# barrieren-a-1.net
KiCad netlist of a schematic drawn in EAGLE
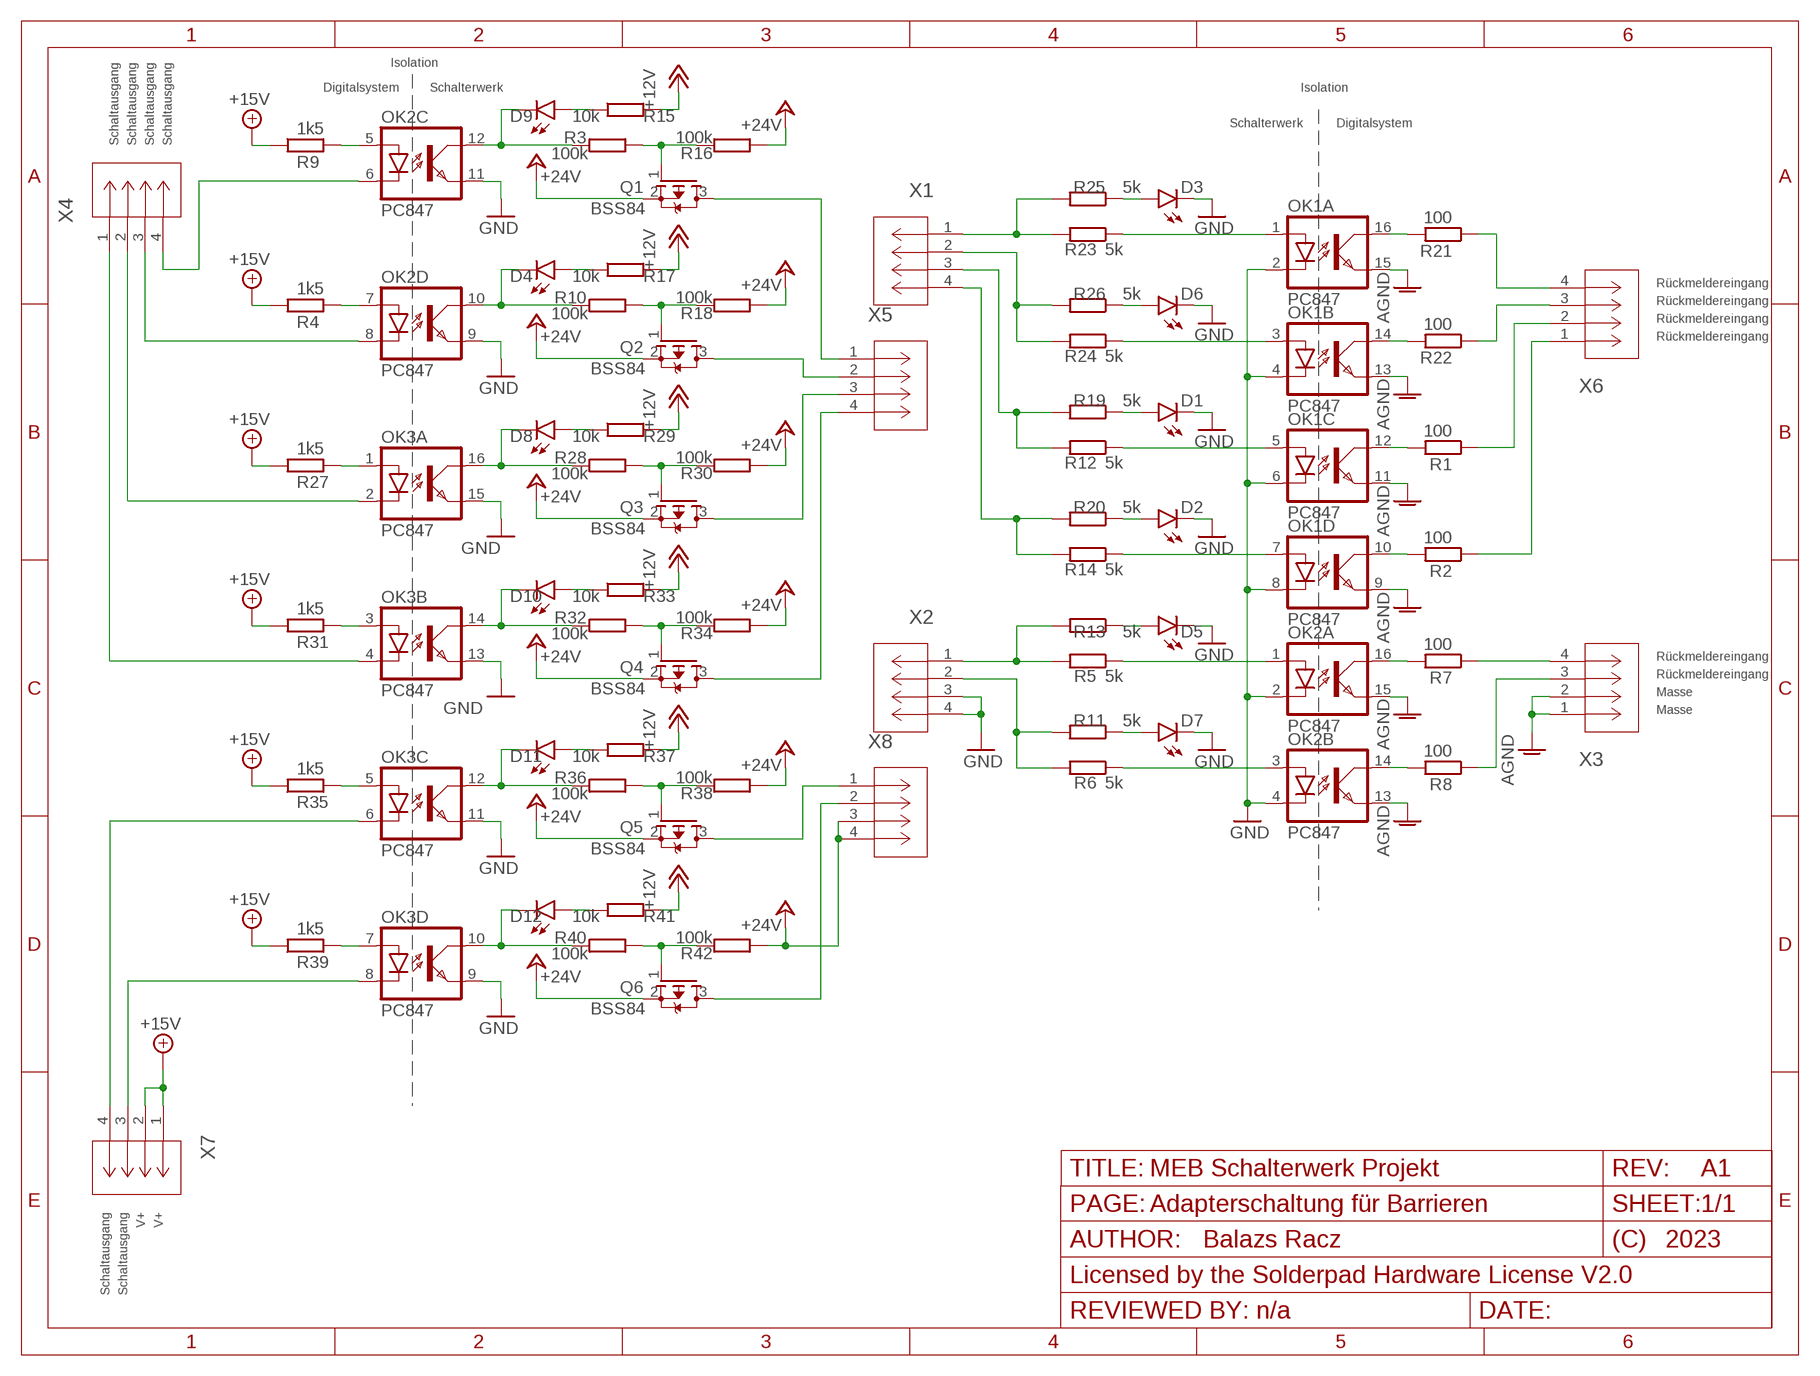
[diagram p0: schematic, sheet 1]

(export (version "E")
  (design (tool "Eeschema 10.0.6"))
  (components
    (comp (ref "D1")
      (value "LEDCHIPLED_0603")
      (footprint "eagle-import:CHIPLED_0603")
      (libsource (lib "eagle-import") (part "LEDCHIPLED_0603"))
    )
    (comp (ref "D2")
      (value "LEDCHIPLED_0603")
      (footprint "eagle-import:CHIPLED_0603")
      (libsource (lib "eagle-import") (part "LEDCHIPLED_0603"))
    )
    (comp (ref "D3")
      (value "LEDCHIPLED_0603")
      (footprint "eagle-import:CHIPLED_0603")
      (libsource (lib "eagle-import") (part "LEDCHIPLED_0603"))
    )
    (comp (ref "D4")
      (value "LEDCHIPLED_0603")
      (footprint "eagle-import:CHIPLED_0603")
      (libsource (lib "eagle-import") (part "LEDCHIPLED_0603"))
    )
    (comp (ref "D5")
      (value "LEDCHIPLED_0603")
      (footprint "eagle-import:CHIPLED_0603")
      (libsource (lib "eagle-import") (part "LEDCHIPLED_0603"))
    )
    (comp (ref "D6")
      (value "LEDCHIPLED_0603")
      (footprint "eagle-import:CHIPLED_0603")
      (libsource (lib "eagle-import") (part "LEDCHIPLED_0603"))
    )
    (comp (ref "D7")
      (value "LEDCHIPLED_0603")
      (footprint "eagle-import:CHIPLED_0603")
      (libsource (lib "eagle-import") (part "LEDCHIPLED_0603"))
    )
    (comp (ref "D8")
      (value "LEDCHIPLED_0603")
      (footprint "eagle-import:CHIPLED_0603")
      (libsource (lib "eagle-import") (part "LEDCHIPLED_0603"))
    )
    (comp (ref "D9")
      (value "LEDCHIPLED_0603")
      (footprint "eagle-import:CHIPLED_0603")
      (libsource (lib "eagle-import") (part "LEDCHIPLED_0603"))
    )
    (comp (ref "D10")
      (value "LEDCHIPLED_0603")
      (footprint "eagle-import:CHIPLED_0603")
      (libsource (lib "eagle-import") (part "LEDCHIPLED_0603"))
    )
    (comp (ref "D11")
      (value "LEDCHIPLED_0603")
      (footprint "eagle-import:CHIPLED_0603")
      (libsource (lib "eagle-import") (part "LEDCHIPLED_0603"))
    )
    (comp (ref "D12")
      (value "LEDCHIPLED_0603")
      (footprint "eagle-import:CHIPLED_0603")
      (libsource (lib "eagle-import") (part "LEDCHIPLED_0603"))
    )
    (comp (ref "OK1")
      (value "PC847")
      (footprint "eagle-import:DIL16")
      (libsource (lib "eagle-import") (part "PC847"))
    )
    (comp (ref "OK2")
      (value "PC847")
      (footprint "eagle-import:DIL16")
      (libsource (lib "eagle-import") (part "PC847"))
    )
    (comp (ref "OK3")
      (value "PC847")
      (footprint "eagle-import:DIL16")
      (libsource (lib "eagle-import") (part "PC847"))
    )
    (comp (ref "Q1")
      (value "BSS84")
      (footprint "eagle-import:SOT23-PCH")
      (libsource (lib "eagle-import") (part "BSS84"))
    )
    (comp (ref "Q2")
      (value "BSS84")
      (footprint "eagle-import:SOT23-PCH")
      (libsource (lib "eagle-import") (part "BSS84"))
    )
    (comp (ref "Q3")
      (value "BSS84")
      (footprint "eagle-import:SOT23-PCH")
      (libsource (lib "eagle-import") (part "BSS84"))
    )
    (comp (ref "Q4")
      (value "BSS84")
      (footprint "eagle-import:SOT23-PCH")
      (libsource (lib "eagle-import") (part "BSS84"))
    )
    (comp (ref "Q5")
      (value "BSS84")
      (footprint "eagle-import:SOT23-PCH")
      (libsource (lib "eagle-import") (part "BSS84"))
    )
    (comp (ref "Q6")
      (value "BSS84")
      (footprint "eagle-import:SOT23-PCH")
      (libsource (lib "eagle-import") (part "BSS84"))
    )
    (comp (ref "R1")
      (value "100")
      (footprint "eagle-import:R0805")
      (libsource (lib "eagle-import") (part "R-EU_R0805"))
    )
    (comp (ref "R2")
      (value "100")
      (footprint "eagle-import:R0805")
      (libsource (lib "eagle-import") (part "R-EU_R0805"))
    )
    (comp (ref "R3")
      (value "100k")
      (footprint "eagle-import:R0805")
      (libsource (lib "eagle-import") (part "R-EU_R0805"))
    )
    (comp (ref "R4")
      (value "1k5")
      (footprint "eagle-import:R0805")
      (libsource (lib "eagle-import") (part "R-EU_R0805"))
    )
    (comp (ref "R5")
      (value "5k")
      (footprint "eagle-import:R0805")
      (libsource (lib "eagle-import") (part "R-EU_R0805"))
    )
    (comp (ref "R6")
      (value "5k")
      (footprint "eagle-import:R0805")
      (libsource (lib "eagle-import") (part "R-EU_R0805"))
    )
    (comp (ref "R7")
      (value "100")
      (footprint "eagle-import:R0805")
      (libsource (lib "eagle-import") (part "R-EU_R0805"))
    )
    (comp (ref "R8")
      (value "100")
      (footprint "eagle-import:R0805")
      (libsource (lib "eagle-import") (part "R-EU_R0805"))
    )
    (comp (ref "R9")
      (value "1k5")
      (footprint "eagle-import:R0805")
      (libsource (lib "eagle-import") (part "R-EU_R0805"))
    )
    (comp (ref "R10")
      (value "100k")
      (footprint "eagle-import:R0805")
      (libsource (lib "eagle-import") (part "R-EU_R0805"))
    )
    (comp (ref "R11")
      (value "5k")
      (footprint "eagle-import:R0805")
      (libsource (lib "eagle-import") (part "R-EU_R0805"))
    )
    (comp (ref "R12")
      (value "5k")
      (footprint "eagle-import:R0805")
      (libsource (lib "eagle-import") (part "R-EU_R0805"))
    )
    (comp (ref "R13")
      (value "5k")
      (footprint "eagle-import:R0805")
      (libsource (lib "eagle-import") (part "R-EU_R0805"))
    )
    (comp (ref "R14")
      (value "5k")
      (footprint "eagle-import:R0805")
      (libsource (lib "eagle-import") (part "R-EU_R0805"))
    )
    (comp (ref "R15")
      (value "10k")
      (footprint "eagle-import:R0805")
      (libsource (lib "eagle-import") (part "R-EU_R0805"))
    )
    (comp (ref "R16")
      (value "100k")
      (footprint "eagle-import:R0805")
      (libsource (lib "eagle-import") (part "R-EU_R0805"))
    )
    (comp (ref "R17")
      (value "10k")
      (footprint "eagle-import:R0805")
      (libsource (lib "eagle-import") (part "R-EU_R0805"))
    )
    (comp (ref "R18")
      (value "100k")
      (footprint "eagle-import:R0805")
      (libsource (lib "eagle-import") (part "R-EU_R0805"))
    )
    (comp (ref "R19")
      (value "5k")
      (footprint "eagle-import:R0805")
      (libsource (lib "eagle-import") (part "R-EU_R0805"))
    )
    (comp (ref "R20")
      (value "5k")
      (footprint "eagle-import:R0805")
      (libsource (lib "eagle-import") (part "R-EU_R0805"))
    )
    (comp (ref "R21")
      (value "100")
      (footprint "eagle-import:R0805")
      (libsource (lib "eagle-import") (part "R-EU_R0805"))
    )
    (comp (ref "R22")
      (value "100")
      (footprint "eagle-import:R0805")
      (libsource (lib "eagle-import") (part "R-EU_R0805"))
    )
    (comp (ref "R23")
      (value "5k")
      (footprint "eagle-import:R0805")
      (libsource (lib "eagle-import") (part "R-EU_R0805"))
    )
    (comp (ref "R24")
      (value "5k")
      (footprint "eagle-import:R0805")
      (libsource (lib "eagle-import") (part "R-EU_R0805"))
    )
    (comp (ref "R25")
      (value "5k")
      (footprint "eagle-import:R0805")
      (libsource (lib "eagle-import") (part "R-EU_R0805"))
    )
    (comp (ref "R26")
      (value "5k")
      (footprint "eagle-import:R0805")
      (libsource (lib "eagle-import") (part "R-EU_R0805"))
    )
    (comp (ref "R27")
      (value "1k5")
      (footprint "eagle-import:R0805")
      (libsource (lib "eagle-import") (part "R-EU_R0805"))
    )
    (comp (ref "R28")
      (value "100k")
      (footprint "eagle-import:R0805")
      (libsource (lib "eagle-import") (part "R-EU_R0805"))
    )
    (comp (ref "R29")
      (value "10k")
      (footprint "eagle-import:R0805")
      (libsource (lib "eagle-import") (part "R-EU_R0805"))
    )
    (comp (ref "R30")
      (value "100k")
      (footprint "eagle-import:R0805")
      (libsource (lib "eagle-import") (part "R-EU_R0805"))
    )
    (comp (ref "R31")
      (value "1k5")
      (footprint "eagle-import:R0805")
      (libsource (lib "eagle-import") (part "R-EU_R0805"))
    )
    (comp (ref "R32")
      (value "100k")
      (footprint "eagle-import:R0805")
      (libsource (lib "eagle-import") (part "R-EU_R0805"))
    )
    (comp (ref "R33")
      (value "10k")
      (footprint "eagle-import:R0805")
      (libsource (lib "eagle-import") (part "R-EU_R0805"))
    )
    (comp (ref "R34")
      (value "100k")
      (footprint "eagle-import:R0805")
      (libsource (lib "eagle-import") (part "R-EU_R0805"))
    )
    (comp (ref "R35")
      (value "1k5")
      (footprint "eagle-import:R0805")
      (libsource (lib "eagle-import") (part "R-EU_R0805"))
    )
    (comp (ref "R36")
      (value "100k")
      (footprint "eagle-import:R0805")
      (libsource (lib "eagle-import") (part "R-EU_R0805"))
    )
    (comp (ref "R37")
      (value "10k")
      (footprint "eagle-import:R0805")
      (libsource (lib "eagle-import") (part "R-EU_R0805"))
    )
    (comp (ref "R38")
      (value "100k")
      (footprint "eagle-import:R0805")
      (libsource (lib "eagle-import") (part "R-EU_R0805"))
    )
    (comp (ref "R39")
      (value "1k5")
      (footprint "eagle-import:R0805")
      (libsource (lib "eagle-import") (part "R-EU_R0805"))
    )
    (comp (ref "R40")
      (value "100k")
      (footprint "eagle-import:R0805")
      (libsource (lib "eagle-import") (part "R-EU_R0805"))
    )
    (comp (ref "R41")
      (value "10k")
      (footprint "eagle-import:R0805")
      (libsource (lib "eagle-import") (part "R-EU_R0805"))
    )
    (comp (ref "R42")
      (value "100k")
      (footprint "eagle-import:R0805")
      (libsource (lib "eagle-import") (part "R-EU_R0805"))
    )
    (comp (ref "X1")
      (value "PHNX_4P_350CONN_1984989_PXC")
      (footprint "eagle-import:PHNX_4P_350")
      (fields
        (field (name "MANUFACTURER_PART_NUMBER") "1984989")
        (field (name "COPYRIGHT") "Copyright (C) 2023 Ultra Librarian. All rights reserved.")
      )
      (libsource (lib "eagle-import") (part "PHNX_4P_350CONN_1984989_PXC"))
    )
    (comp (ref "X2")
      (value "PHNX_4P_350CONN_1984989_PXC")
      (footprint "eagle-import:PHNX_4P_350")
      (fields
        (field (name "MANUFACTURER_PART_NUMBER") "1984989")
        (field (name "COPYRIGHT") "Copyright (C) 2023 Ultra Librarian. All rights reserved.")
      )
      (libsource (lib "eagle-import") (part "PHNX_4P_350CONN_1984989_PXC"))
    )
    (comp (ref "X3")
      (value "PHNX_4P_350CONN_1984989_PXC")
      (footprint "eagle-import:PHNX_4P_350")
      (fields
        (field (name "MANUFACTURER_PART_NUMBER") "1984989")
        (field (name "COPYRIGHT") "Copyright (C) 2023 Ultra Librarian. All rights reserved.")
      )
      (libsource (lib "eagle-import") (part "PHNX_4P_350CONN_1984989_PXC"))
    )
    (comp (ref "X4")
      (value "PHNX_4P_350CONN_1984989_PXC")
      (footprint "eagle-import:PHNX_4P_350")
      (fields
        (field (name "MANUFACTURER_PART_NUMBER") "1984989")
        (field (name "COPYRIGHT") "Copyright (C) 2023 Ultra Librarian. All rights reserved.")
      )
      (libsource (lib "eagle-import") (part "PHNX_4P_350CONN_1984989_PXC"))
    )
    (comp (ref "X5")
      (value "PHNX_4P_350CONN_1984989_PXC")
      (footprint "eagle-import:PHNX_4P_350")
      (fields
        (field (name "MANUFACTURER_PART_NUMBER") "1984989")
        (field (name "COPYRIGHT") "Copyright (C) 2023 Ultra Librarian. All rights reserved.")
      )
      (libsource (lib "eagle-import") (part "PHNX_4P_350CONN_1984989_PXC"))
    )
    (comp (ref "X6")
      (value "PHNX_4P_350CONN_1984989_PXC")
      (footprint "eagle-import:PHNX_4P_350")
      (fields
        (field (name "MANUFACTURER_PART_NUMBER") "1984989")
        (field (name "COPYRIGHT") "Copyright (C) 2023 Ultra Librarian. All rights reserved.")
      )
      (libsource (lib "eagle-import") (part "PHNX_4P_350CONN_1984989_PXC"))
    )
    (comp (ref "X7")
      (value "PHNX_4P_350CONN_1984989_PXC")
      (footprint "eagle-import:PHNX_4P_350")
      (fields
        (field (name "MANUFACTURER_PART_NUMBER") "1984989")
        (field (name "COPYRIGHT") "Copyright (C) 2023 Ultra Librarian. All rights reserved.")
      )
      (libsource (lib "eagle-import") (part "PHNX_4P_350CONN_1984989_PXC"))
    )
    (comp (ref "X8")
      (value "PHNX_4P_350CONN_1984989_PXC")
      (footprint "eagle-import:PHNX_4P_350")
      (fields
        (field (name "MANUFACTURER_PART_NUMBER") "1984989")
        (field (name "COPYRIGHT") "Copyright (C) 2023 Ultra Librarian. All rights reserved.")
      )
      (libsource (lib "eagle-import") (part "PHNX_4P_350CONN_1984989_PXC"))
    )
  )
  (nets
    (net (code "1") (name "+12V") (class "Default")
      (node (ref "R15") (pin "2") (pinfunction "2_2") (pintype "passive"))
      (node (ref "R17") (pin "2") (pinfunction "2_2") (pintype "passive"))
      (node (ref "R29") (pin "2") (pinfunction "2_2") (pintype "passive"))
      (node (ref "R33") (pin "2") (pinfunction "2_2") (pintype "passive"))
      (node (ref "R37") (pin "2") (pinfunction "2_2") (pintype "passive"))
      (node (ref "R41") (pin "2") (pinfunction "2_2") (pintype "passive"))
    )
    (net (code "2") (name "+15V") (class "Default")
      (node (ref "R27") (pin "1") (pinfunction "1_1") (pintype "passive"))
      (node (ref "R31") (pin "1") (pinfunction "1_1") (pintype "passive"))
      (node (ref "R35") (pin "1") (pinfunction "1_1") (pintype "passive"))
      (node (ref "R39") (pin "1") (pinfunction "1_1") (pintype "passive"))
      (node (ref "R4") (pin "1") (pinfunction "1_1") (pintype "passive"))
      (node (ref "R9") (pin "1") (pinfunction "1_1") (pintype "passive"))
      (node (ref "X7") (pin "1") (pinfunction "1_1") (pintype "passive"))
      (node (ref "X7") (pin "2") (pinfunction "2_2") (pintype "passive"))
    )
    (net (code "3") (name "+24V") (class "Default")
      (node (ref "Q1") (pin "2") (pinfunction "S_2") (pintype "passive"))
      (node (ref "Q2") (pin "2") (pinfunction "S_2") (pintype "passive"))
      (node (ref "Q3") (pin "2") (pinfunction "S_2") (pintype "passive"))
      (node (ref "Q4") (pin "2") (pinfunction "S_2") (pintype "passive"))
      (node (ref "Q5") (pin "2") (pinfunction "S_2") (pintype "passive"))
      (node (ref "Q6") (pin "2") (pinfunction "S_2") (pintype "passive"))
      (node (ref "R16") (pin "2") (pinfunction "2_2") (pintype "passive"))
      (node (ref "R18") (pin "2") (pinfunction "2_2") (pintype "passive"))
      (node (ref "R30") (pin "2") (pinfunction "2_2") (pintype "passive"))
      (node (ref "R34") (pin "2") (pinfunction "2_2") (pintype "passive"))
      (node (ref "R38") (pin "2") (pinfunction "2_2") (pintype "passive"))
      (node (ref "R42") (pin "2") (pinfunction "2_2") (pintype "passive"))
      (node (ref "X8") (pin "3") (pinfunction "3_3") (pintype "passive"))
      (node (ref "X8") (pin "4") (pinfunction "4_4") (pintype "passive"))
    )
    (net (code "4") (name "AGND") (class "Default")
      (node (ref "OK1") (pin "11") (pinfunction "EMIT_11") (pintype "passive"))
      (node (ref "OK1") (pin "13") (pinfunction "EMIT_13") (pintype "passive"))
      (node (ref "OK1") (pin "15") (pinfunction "EMIT_15") (pintype "passive"))
      (node (ref "OK1") (pin "9") (pinfunction "EMIT_9") (pintype "passive"))
      (node (ref "OK2") (pin "13") (pinfunction "EMIT_13") (pintype "passive"))
      (node (ref "OK2") (pin "15") (pinfunction "EMIT_15") (pintype "passive"))
      (node (ref "X3") (pin "1") (pinfunction "1_1") (pintype "passive"))
      (node (ref "X3") (pin "2") (pinfunction "2_2") (pintype "passive"))
    )
    (net (code "5") (name "GND") (class "Default")
      (node (ref "D1") (pin "C") (pinfunction "C_C") (pintype "passive"))
      (node (ref "D2") (pin "C") (pinfunction "C_C") (pintype "passive"))
      (node (ref "D3") (pin "C") (pinfunction "C_C") (pintype "passive"))
      (node (ref "D5") (pin "C") (pinfunction "C_C") (pintype "passive"))
      (node (ref "D6") (pin "C") (pinfunction "C_C") (pintype "passive"))
      (node (ref "D7") (pin "C") (pinfunction "C_C") (pintype "passive"))
      (node (ref "OK1") (pin "2") (pinfunction "C_2") (pintype "passive"))
      (node (ref "OK1") (pin "4") (pinfunction "C_4") (pintype "passive"))
      (node (ref "OK1") (pin "6") (pinfunction "C_6") (pintype "passive"))
      (node (ref "OK1") (pin "8") (pinfunction "C_8") (pintype "passive"))
      (node (ref "OK2") (pin "11") (pinfunction "EMIT_11") (pintype "passive"))
      (node (ref "OK2") (pin "2") (pinfunction "C_2") (pintype "passive"))
      (node (ref "OK2") (pin "4") (pinfunction "C_4") (pintype "passive"))
      (node (ref "OK2") (pin "9") (pinfunction "EMIT_9") (pintype "passive"))
      (node (ref "OK3") (pin "11") (pinfunction "EMIT_11") (pintype "passive"))
      (node (ref "OK3") (pin "13") (pinfunction "EMIT_13") (pintype "passive"))
      (node (ref "OK3") (pin "15") (pinfunction "EMIT_15") (pintype "passive"))
      (node (ref "OK3") (pin "9") (pinfunction "EMIT_9") (pintype "passive"))
      (node (ref "X2") (pin "3") (pinfunction "3_3") (pintype "passive"))
      (node (ref "X2") (pin "4") (pinfunction "4_4") (pintype "passive"))
    )
    (net (code "6") (name "Net-(D1-PadA)") (class "Default")
      (node (ref "D1") (pin "A") (pinfunction "A_A") (pintype "passive"))
      (node (ref "R19") (pin "1") (pinfunction "1_1") (pintype "passive"))
    )
    (net (code "7") (name "Net-(D2-PadA)") (class "Default")
      (node (ref "D2") (pin "A") (pinfunction "A_A") (pintype "passive"))
      (node (ref "R20") (pin "1") (pinfunction "1_1") (pintype "passive"))
    )
    (net (code "8") (name "Net-(D3-PadA)") (class "Default")
      (node (ref "D3") (pin "A") (pinfunction "A_A") (pintype "passive"))
      (node (ref "R25") (pin "1") (pinfunction "1_1") (pintype "passive"))
    )
    (net (code "9") (name "Net-(D4-PadA)") (class "Default")
      (node (ref "D4") (pin "A") (pinfunction "A_A") (pintype "passive"))
      (node (ref "R17") (pin "1") (pinfunction "1_1") (pintype "passive"))
    )
    (net (code "10") (name "Net-(D5-PadA)") (class "Default")
      (node (ref "D5") (pin "A") (pinfunction "A_A") (pintype "passive"))
      (node (ref "R13") (pin "1") (pinfunction "1_1") (pintype "passive"))
    )
    (net (code "11") (name "Net-(D6-PadA)") (class "Default")
      (node (ref "D6") (pin "A") (pinfunction "A_A") (pintype "passive"))
      (node (ref "R26") (pin "1") (pinfunction "1_1") (pintype "passive"))
    )
    (net (code "12") (name "Net-(D7-PadA)") (class "Default")
      (node (ref "D7") (pin "A") (pinfunction "A_A") (pintype "passive"))
      (node (ref "R11") (pin "1") (pinfunction "1_1") (pintype "passive"))
    )
    (net (code "13") (name "Net-(D8-PadA)") (class "Default")
      (node (ref "D8") (pin "A") (pinfunction "A_A") (pintype "passive"))
      (node (ref "R29") (pin "1") (pinfunction "1_1") (pintype "passive"))
    )
    (net (code "14") (name "Net-(D9-PadA)") (class "Default")
      (node (ref "D9") (pin "A") (pinfunction "A_A") (pintype "passive"))
      (node (ref "R15") (pin "1") (pinfunction "1_1") (pintype "passive"))
    )
    (net (code "15") (name "Net-(D10-PadA)") (class "Default")
      (node (ref "D10") (pin "A") (pinfunction "A_A") (pintype "passive"))
      (node (ref "R33") (pin "1") (pinfunction "1_1") (pintype "passive"))
    )
    (net (code "16") (name "Net-(D11-PadA)") (class "Default")
      (node (ref "D11") (pin "A") (pinfunction "A_A") (pintype "passive"))
      (node (ref "R37") (pin "1") (pinfunction "1_1") (pintype "passive"))
    )
    (net (code "17") (name "Net-(D12-PadA)") (class "Default")
      (node (ref "D12") (pin "A") (pinfunction "A_A") (pintype "passive"))
      (node (ref "R41") (pin "1") (pinfunction "1_1") (pintype "passive"))
    )
    (net (code "18") (name "Net-(OK1A-A)") (class "Default")
      (node (ref "OK1") (pin "1") (pinfunction "A_1") (pintype "passive"))
      (node (ref "R23") (pin "1") (pinfunction "1_1") (pintype "passive"))
    )
    (net (code "19") (name "Net-(OK1A-COL)") (class "Default")
      (node (ref "OK1") (pin "16") (pinfunction "COL_16") (pintype "passive"))
      (node (ref "R21") (pin "2") (pinfunction "2_2") (pintype "passive"))
    )
    (net (code "20") (name "Net-(OK1B-A)") (class "Default")
      (node (ref "OK1") (pin "3") (pinfunction "A_3") (pintype "passive"))
      (node (ref "R24") (pin "1") (pinfunction "1_1") (pintype "passive"))
    )
    (net (code "21") (name "Net-(OK1B-COL)") (class "Default")
      (node (ref "OK1") (pin "14") (pinfunction "COL_14") (pintype "passive"))
      (node (ref "R22") (pin "2") (pinfunction "2_2") (pintype "passive"))
    )
    (net (code "22") (name "Net-(OK1C-A)") (class "Default")
      (node (ref "OK1") (pin "5") (pinfunction "A_5") (pintype "passive"))
      (node (ref "R12") (pin "1") (pinfunction "1_1") (pintype "passive"))
    )
    (net (code "23") (name "Net-(OK1C-COL)") (class "Default")
      (node (ref "OK1") (pin "12") (pinfunction "COL_12") (pintype "passive"))
      (node (ref "R1") (pin "2") (pinfunction "2_2") (pintype "passive"))
    )
    (net (code "24") (name "Net-(OK1D-A)") (class "Default")
      (node (ref "OK1") (pin "7") (pinfunction "A_7") (pintype "passive"))
      (node (ref "R14") (pin "1") (pinfunction "1_1") (pintype "passive"))
    )
    (net (code "25") (name "Net-(OK1D-COL)") (class "Default")
      (node (ref "OK1") (pin "10") (pinfunction "COL_10") (pintype "passive"))
      (node (ref "R2") (pin "2") (pinfunction "2_2") (pintype "passive"))
    )
    (net (code "26") (name "Net-(OK2A-A)") (class "Default")
      (node (ref "OK2") (pin "1") (pinfunction "A_1") (pintype "passive"))
      (node (ref "R5") (pin "1") (pinfunction "1_1") (pintype "passive"))
    )
    (net (code "27") (name "Net-(OK2A-COL)") (class "Default")
      (node (ref "OK2") (pin "16") (pinfunction "COL_16") (pintype "passive"))
      (node (ref "R7") (pin "2") (pinfunction "2_2") (pintype "passive"))
    )
    (net (code "28") (name "Net-(OK2B-A)") (class "Default")
      (node (ref "OK2") (pin "3") (pinfunction "A_3") (pintype "passive"))
      (node (ref "R6") (pin "1") (pinfunction "1_1") (pintype "passive"))
    )
    (net (code "29") (name "Net-(OK2B-COL)") (class "Default")
      (node (ref "OK2") (pin "14") (pinfunction "COL_14") (pintype "passive"))
      (node (ref "R8") (pin "2") (pinfunction "2_2") (pintype "passive"))
    )
    (net (code "30") (name "Net-(OK2C-A)") (class "Default")
      (node (ref "OK2") (pin "5") (pinfunction "A_5") (pintype "passive"))
      (node (ref "R9") (pin "2") (pinfunction "2_2") (pintype "passive"))
    )
    (net (code "31") (name "Net-(OK2C-C)") (class "Default")
      (node (ref "OK2") (pin "6") (pinfunction "C_6") (pintype "passive"))
      (node (ref "X4") (pin "4") (pinfunction "4_4") (pintype "passive"))
    )
    (net (code "32") (name "Net-(OK2C-COL)") (class "Default")
      (node (ref "D9") (pin "C") (pinfunction "C_C") (pintype "passive"))
      (node (ref "OK2") (pin "12") (pinfunction "COL_12") (pintype "passive"))
      (node (ref "R3") (pin "2") (pinfunction "2_2") (pintype "passive"))
    )
    (net (code "33") (name "Net-(OK2D-A)") (class "Default")
      (node (ref "OK2") (pin "7") (pinfunction "A_7") (pintype "passive"))
      (node (ref "R4") (pin "2") (pinfunction "2_2") (pintype "passive"))
    )
    (net (code "34") (name "Net-(OK2D-C)") (class "Default")
      (node (ref "OK2") (pin "8") (pinfunction "C_8") (pintype "passive"))
      (node (ref "X4") (pin "3") (pinfunction "3_3") (pintype "passive"))
    )
    (net (code "35") (name "Net-(OK2D-COL)") (class "Default")
      (node (ref "D4") (pin "C") (pinfunction "C_C") (pintype "passive"))
      (node (ref "OK2") (pin "10") (pinfunction "COL_10") (pintype "passive"))
      (node (ref "R10") (pin "2") (pinfunction "2_2") (pintype "passive"))
    )
    (net (code "36") (name "Net-(OK3A-A)") (class "Default")
      (node (ref "OK3") (pin "1") (pinfunction "A_1") (pintype "passive"))
      (node (ref "R27") (pin "2") (pinfunction "2_2") (pintype "passive"))
    )
    (net (code "37") (name "Net-(OK3A-C)") (class "Default")
      (node (ref "OK3") (pin "2") (pinfunction "C_2") (pintype "passive"))
      (node (ref "X4") (pin "2") (pinfunction "2_2") (pintype "passive"))
    )
    (net (code "38") (name "Net-(OK3A-COL)") (class "Default")
      (node (ref "D8") (pin "C") (pinfunction "C_C") (pintype "passive"))
      (node (ref "OK3") (pin "16") (pinfunction "COL_16") (pintype "passive"))
      (node (ref "R28") (pin "2") (pinfunction "2_2") (pintype "passive"))
    )
    (net (code "39") (name "Net-(OK3B-A)") (class "Default")
      (node (ref "OK3") (pin "3") (pinfunction "A_3") (pintype "passive"))
      (node (ref "R31") (pin "2") (pinfunction "2_2") (pintype "passive"))
    )
    (net (code "40") (name "Net-(OK3B-C)") (class "Default")
      (node (ref "OK3") (pin "4") (pinfunction "C_4") (pintype "passive"))
      (node (ref "X4") (pin "1") (pinfunction "1_1") (pintype "passive"))
    )
    (net (code "41") (name "Net-(OK3B-COL)") (class "Default")
      (node (ref "D10") (pin "C") (pinfunction "C_C") (pintype "passive"))
      (node (ref "OK3") (pin "14") (pinfunction "COL_14") (pintype "passive"))
      (node (ref "R32") (pin "2") (pinfunction "2_2") (pintype "passive"))
    )
    (net (code "42") (name "Net-(OK3C-A)") (class "Default")
      (node (ref "OK3") (pin "5") (pinfunction "A_5") (pintype "passive"))
      (node (ref "R35") (pin "2") (pinfunction "2_2") (pintype "passive"))
    )
    (net (code "43") (name "Net-(OK3C-C)") (class "Default")
      (node (ref "OK3") (pin "6") (pinfunction "C_6") (pintype "passive"))
      (node (ref "X7") (pin "4") (pinfunction "4_4") (pintype "passive"))
    )
    (net (code "44") (name "Net-(OK3C-COL)") (class "Default")
      (node (ref "D11") (pin "C") (pinfunction "C_C") (pintype "passive"))
      (node (ref "OK3") (pin "12") (pinfunction "COL_12") (pintype "passive"))
      (node (ref "R36") (pin "2") (pinfunction "2_2") (pintype "passive"))
    )
    (net (code "45") (name "Net-(OK3D-A)") (class "Default")
      (node (ref "OK3") (pin "7") (pinfunction "A_7") (pintype "passive"))
      (node (ref "R39") (pin "2") (pinfunction "2_2") (pintype "passive"))
    )
    (net (code "46") (name "Net-(OK3D-C)") (class "Default")
      (node (ref "OK3") (pin "8") (pinfunction "C_8") (pintype "passive"))
      (node (ref "X7") (pin "3") (pinfunction "3_3") (pintype "passive"))
    )
    (net (code "47") (name "Net-(OK3D-COL)") (class "Default")
      (node (ref "D12") (pin "C") (pinfunction "C_C") (pintype "passive"))
      (node (ref "OK3") (pin "10") (pinfunction "COL_10") (pintype "passive"))
      (node (ref "R40") (pin "2") (pinfunction "2_2") (pintype "passive"))
    )
    (net (code "48") (name "Net-(Q1-D)") (class "Default")
      (node (ref "Q1") (pin "3") (pinfunction "D_3") (pintype "passive"))
      (node (ref "X5") (pin "1") (pinfunction "1_1") (pintype "passive"))
    )
    (net (code "49") (name "Net-(Q1-G)") (class "Default")
      (node (ref "Q1") (pin "1") (pinfunction "G_1") (pintype "passive"))
      (node (ref "R16") (pin "1") (pinfunction "1_1") (pintype "passive"))
      (node (ref "R3") (pin "1") (pinfunction "1_1") (pintype "passive"))
    )
    (net (code "50") (name "Net-(Q2-D)") (class "Default")
      (node (ref "Q2") (pin "3") (pinfunction "D_3") (pintype "passive"))
      (node (ref "X5") (pin "2") (pinfunction "2_2") (pintype "passive"))
    )
    (net (code "51") (name "Net-(Q2-G)") (class "Default")
      (node (ref "Q2") (pin "1") (pinfunction "G_1") (pintype "passive"))
      (node (ref "R10") (pin "1") (pinfunction "1_1") (pintype "passive"))
      (node (ref "R18") (pin "1") (pinfunction "1_1") (pintype "passive"))
    )
    (net (code "52") (name "Net-(Q3-D)") (class "Default")
      (node (ref "Q3") (pin "3") (pinfunction "D_3") (pintype "passive"))
      (node (ref "X5") (pin "3") (pinfunction "3_3") (pintype "passive"))
    )
    (net (code "53") (name "Net-(Q3-G)") (class "Default")
      (node (ref "Q3") (pin "1") (pinfunction "G_1") (pintype "passive"))
      (node (ref "R28") (pin "1") (pinfunction "1_1") (pintype "passive"))
      (node (ref "R30") (pin "1") (pinfunction "1_1") (pintype "passive"))
    )
    (net (code "54") (name "Net-(Q4-D)") (class "Default")
      (node (ref "Q4") (pin "3") (pinfunction "D_3") (pintype "passive"))
      (node (ref "X5") (pin "4") (pinfunction "4_4") (pintype "passive"))
    )
    (net (code "55") (name "Net-(Q4-G)") (class "Default")
      (node (ref "Q4") (pin "1") (pinfunction "G_1") (pintype "passive"))
      (node (ref "R32") (pin "1") (pinfunction "1_1") (pintype "passive"))
      (node (ref "R34") (pin "1") (pinfunction "1_1") (pintype "passive"))
    )
    (net (code "56") (name "Net-(Q5-D)") (class "Default")
      (node (ref "Q5") (pin "3") (pinfunction "D_3") (pintype "passive"))
      (node (ref "X8") (pin "1") (pinfunction "1_1") (pintype "passive"))
    )
    (net (code "57") (name "Net-(Q5-G)") (class "Default")
      (node (ref "Q5") (pin "1") (pinfunction "G_1") (pintype "passive"))
      (node (ref "R36") (pin "1") (pinfunction "1_1") (pintype "passive"))
      (node (ref "R38") (pin "1") (pinfunction "1_1") (pintype "passive"))
    )
    (net (code "58") (name "Net-(Q6-D)") (class "Default")
      (node (ref "Q6") (pin "3") (pinfunction "D_3") (pintype "passive"))
      (node (ref "X8") (pin "2") (pinfunction "2_2") (pintype "passive"))
    )
    (net (code "59") (name "Net-(Q6-G)") (class "Default")
      (node (ref "Q6") (pin "1") (pinfunction "G_1") (pintype "passive"))
      (node (ref "R40") (pin "1") (pinfunction "1_1") (pintype "passive"))
      (node (ref "R42") (pin "1") (pinfunction "1_1") (pintype "passive"))
    )
    (net (code "60") (name "Net-(R1-Pad1)") (class "Default")
      (node (ref "R1") (pin "1") (pinfunction "1_1") (pintype "passive"))
      (node (ref "X6") (pin "2") (pinfunction "2_2") (pintype "passive"))
    )
    (net (code "61") (name "Net-(R2-Pad1)") (class "Default")
      (node (ref "R2") (pin "1") (pinfunction "1_1") (pintype "passive"))
      (node (ref "X6") (pin "1") (pinfunction "1_1") (pintype "passive"))
    )
    (net (code "62") (name "Net-(R7-Pad1)") (class "Default")
      (node (ref "R7") (pin "1") (pinfunction "1_1") (pintype "passive"))
      (node (ref "X3") (pin "4") (pinfunction "4_4") (pintype "passive"))
    )
    (net (code "63") (name "Net-(R8-Pad1)") (class "Default")
      (node (ref "R8") (pin "1") (pinfunction "1_1") (pintype "passive"))
      (node (ref "X3") (pin "3") (pinfunction "3_3") (pintype "passive"))
    )
    (net (code "64") (name "Net-(R11-Pad2)") (class "Default")
      (node (ref "R11") (pin "2") (pinfunction "2_2") (pintype "passive"))
      (node (ref "R6") (pin "2") (pinfunction "2_2") (pintype "passive"))
      (node (ref "X2") (pin "2") (pinfunction "2_2") (pintype "passive"))
    )
    (net (code "65") (name "Net-(R12-Pad2)") (class "Default")
      (node (ref "R12") (pin "2") (pinfunction "2_2") (pintype "passive"))
      (node (ref "R19") (pin "2") (pinfunction "2_2") (pintype "passive"))
      (node (ref "X1") (pin "3") (pinfunction "3_3") (pintype "passive"))
    )
    (net (code "66") (name "Net-(R13-Pad2)") (class "Default")
      (node (ref "R13") (pin "2") (pinfunction "2_2") (pintype "passive"))
      (node (ref "R5") (pin "2") (pinfunction "2_2") (pintype "passive"))
      (node (ref "X2") (pin "1") (pinfunction "1_1") (pintype "passive"))
    )
    (net (code "67") (name "Net-(R14-Pad2)") (class "Default")
      (node (ref "R14") (pin "2") (pinfunction "2_2") (pintype "passive"))
      (node (ref "R20") (pin "2") (pinfunction "2_2") (pintype "passive"))
      (node (ref "X1") (pin "4") (pinfunction "4_4") (pintype "passive"))
    )
    (net (code "68") (name "Net-(R21-Pad1)") (class "Default")
      (node (ref "R21") (pin "1") (pinfunction "1_1") (pintype "passive"))
      (node (ref "X6") (pin "4") (pinfunction "4_4") (pintype "passive"))
    )
    (net (code "69") (name "Net-(R22-Pad1)") (class "Default")
      (node (ref "R22") (pin "1") (pinfunction "1_1") (pintype "passive"))
      (node (ref "X6") (pin "3") (pinfunction "3_3") (pintype "passive"))
    )
    (net (code "70") (name "Net-(R23-Pad2)") (class "Default")
      (node (ref "R23") (pin "2") (pinfunction "2_2") (pintype "passive"))
      (node (ref "R25") (pin "2") (pinfunction "2_2") (pintype "passive"))
      (node (ref "X1") (pin "1") (pinfunction "1_1") (pintype "passive"))
    )
    (net (code "71") (name "Net-(R24-Pad2)") (class "Default")
      (node (ref "R24") (pin "2") (pinfunction "2_2") (pintype "passive"))
      (node (ref "R26") (pin "2") (pinfunction "2_2") (pintype "passive"))
      (node (ref "X1") (pin "2") (pinfunction "2_2") (pintype "passive"))
    )
  )
)
